# TJA1050.net
KiCad netlist of a schematic drawn in Altium Designer
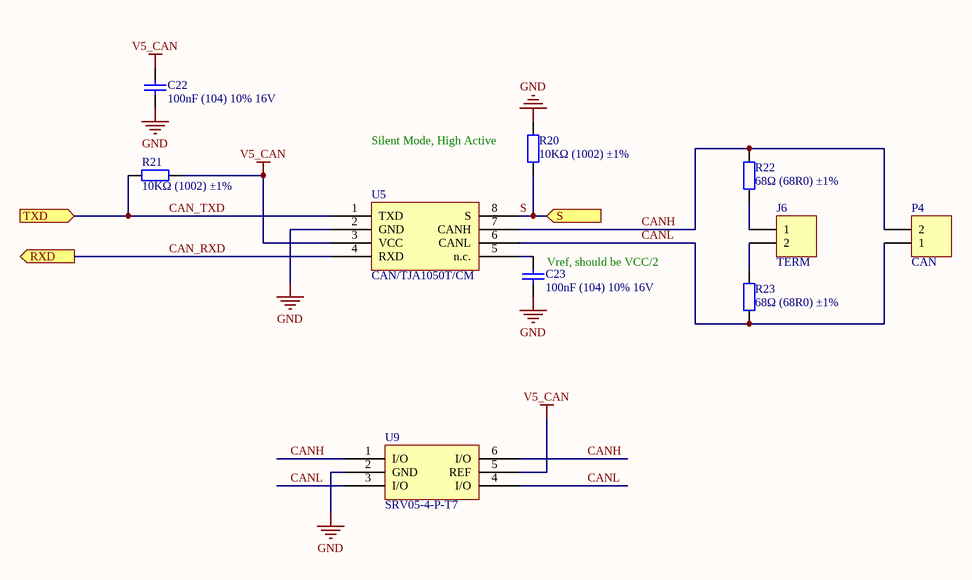
[diagram p0: TJA1050.SchDoc]

(export (version "E")
  (design (tool "Eeschema 10.0.6"))
  (components
    (comp (ref "C22")
      (value "100nF (104) 10% 16V")
      (footprint "0402_C")
      (description "贴片电容")
      (libsource (lib "Miscellaneous Devices LC") (part "0402 100nF (104) 10% 16V"))
    )
    (comp (ref "C23")
      (value "100nF (104) 10% 16V")
      (footprint "0402_C")
      (description "贴片电容")
      (libsource (lib "Miscellaneous Devices LC") (part "0402 100nF (104) 10% 16V"))
    )
    (comp (ref "J6")
      (value "TERM")
      (footprint "HDR1X2")
      (description "Header, 2-Pin")
      (fields (field (name "PUBLISHER") "Altium Limited"))
      (libsource (lib "Miscellaneous Connectors") (part "Header 2"))
    )
    (comp (ref "P4")
      (value "CAN")
      (footprint "WJ2EDGRC-5.08-2PxxR")
      (description "Header, 2-Pin")
      (fields (field (name "PUBLISHER") "Altium Limited"))
      (libsource (lib "") (part "Header 2_1"))
    )
    (comp (ref "R20")
      (value "10KΩ (1002) ±1%")
      (footprint "0402_R")
      (description "贴片电阻")
      (libsource (lib "") (part "0402 10KΩ (1002) 1%_1"))
    )
    (comp (ref "R21")
      (value "10KΩ (1002) ±1%")
      (footprint "0402_R")
      (description "贴片电阻")
      (libsource (lib "Miscellaneous Devices LC") (part "0402 10KΩ (1002) 1%"))
    )
    (comp (ref "R22")
      (value "68Ω (68R0) ±1%")
      (footprint "0603_R")
      (description "贴片电阻")
      (libsource (lib "Miscellaneous Devices LC") (part "0603 68Ω (68R0) 1%"))
    )
    (comp (ref "R23")
      (value "68Ω (68R0) ±1%")
      (footprint "0603_R")
      (description "贴片电阻")
      (libsource (lib "Miscellaneous Devices LC") (part "0603 68Ω (68R0) 1%"))
    )
    (comp (ref "U5")
      (value "CAN/TJA1050T/CM")
      (footprint "SOIC-8_150mil")
      (description "CAN")
      (libsource (lib "Miscellaneous Devices LC") (part "CAN/TJA1050T/CM_[C6952]"))
    )
    (comp (ref "U9")
      (value "SRV05-4-P-T7")
      (footprint "SOT-23-6")
      (description "TVS")
      (libsource (lib "Miscellaneous Devices LC") (part "SRV05-4-P-T7_[C85364]"))
    )
  )
  (nets
    (net (code "1") (name "/CANH") (class "Default")
      (node (ref "P4") (pin "2") (pinfunction "2_2") (pintype "passive"))
      (node (ref "R22") (pin "2") (pinfunction "2_2") (pintype "passive"))
      (node (ref "U5") (pin "7") (pinfunction "CANH_7") (pintype "passive"))
      (node (ref "U9") (pin "1") (pinfunction "I/O_1") (pintype "passive"))
      (node (ref "U9") (pin "6") (pinfunction "I/O_6") (pintype "passive"))
    )
    (net (code "2") (name "/CANL") (class "Default")
      (node (ref "P4") (pin "1") (pinfunction "1_1") (pintype "passive"))
      (node (ref "R23") (pin "1") (pinfunction "1_1") (pintype "passive"))
      (node (ref "U5") (pin "6") (pinfunction "CANL_6") (pintype "passive"))
      (node (ref "U9") (pin "3") (pinfunction "I/O_3") (pintype "passive"))
      (node (ref "U9") (pin "4") (pinfunction "I/O_4") (pintype "passive"))
    )
    (net (code "3") (name "/CAN_RXD") (class "Default")
      (node (ref "U5") (pin "4") (pinfunction "RXD_4") (pintype "passive"))
    )
    (net (code "4") (name "/CAN_TXD") (class "Default")
      (node (ref "R21") (pin "2") (pinfunction "2_2") (pintype "passive"))
      (node (ref "U5") (pin "1") (pinfunction "TXD_1") (pintype "passive"))
    )
    (net (code "5") (name "/S") (class "Default")
      (node (ref "R20") (pin "1") (pinfunction "1_1") (pintype "passive"))
      (node (ref "U5") (pin "8") (pinfunction "S_8") (pintype "passive"))
    )
    (net (code "6") (name "GND") (class "Default")
      (node (ref "C22") (pin "1") (pinfunction "1_1") (pintype "passive"))
      (node (ref "C23") (pin "1") (pinfunction "1_1") (pintype "passive"))
      (node (ref "R20") (pin "2") (pinfunction "2_2") (pintype "passive"))
      (node (ref "U5") (pin "2") (pinfunction "GND_2") (pintype "passive"))
      (node (ref "U9") (pin "2") (pinfunction "GND_2") (pintype "passive"))
    )
    (net (code "7") (name "Net-(J6-Pad1)") (class "Default")
      (node (ref "J6") (pin "1") (pinfunction "1_1") (pintype "passive"))
      (node (ref "R22") (pin "1") (pinfunction "1_1") (pintype "passive"))
    )
    (net (code "8") (name "Net-(J6-Pad2)") (class "Default")
      (node (ref "J6") (pin "2") (pinfunction "2_2") (pintype "passive"))
      (node (ref "R23") (pin "2") (pinfunction "2_2") (pintype "passive"))
    )
    (net (code "9") (name "Net-(U5-n.c.)") (class "Default")
      (node (ref "C23") (pin "2") (pinfunction "2_2") (pintype "passive"))
      (node (ref "U5") (pin "5") (pinfunction "n.c._5") (pintype "passive"))
    )
    (net (code "10") (name "V5_CAN") (class "Default")
      (node (ref "C22") (pin "2") (pinfunction "2_2") (pintype "passive"))
      (node (ref "R21") (pin "1") (pinfunction "1_1") (pintype "passive"))
      (node (ref "U5") (pin "3") (pinfunction "VCC_3") (pintype "passive"))
      (node (ref "U9") (pin "5") (pinfunction "REF_5") (pintype "passive"))
    )
  )
)
